# chiclet.net
KiCad netlist of a schematic drawn in EAGLE
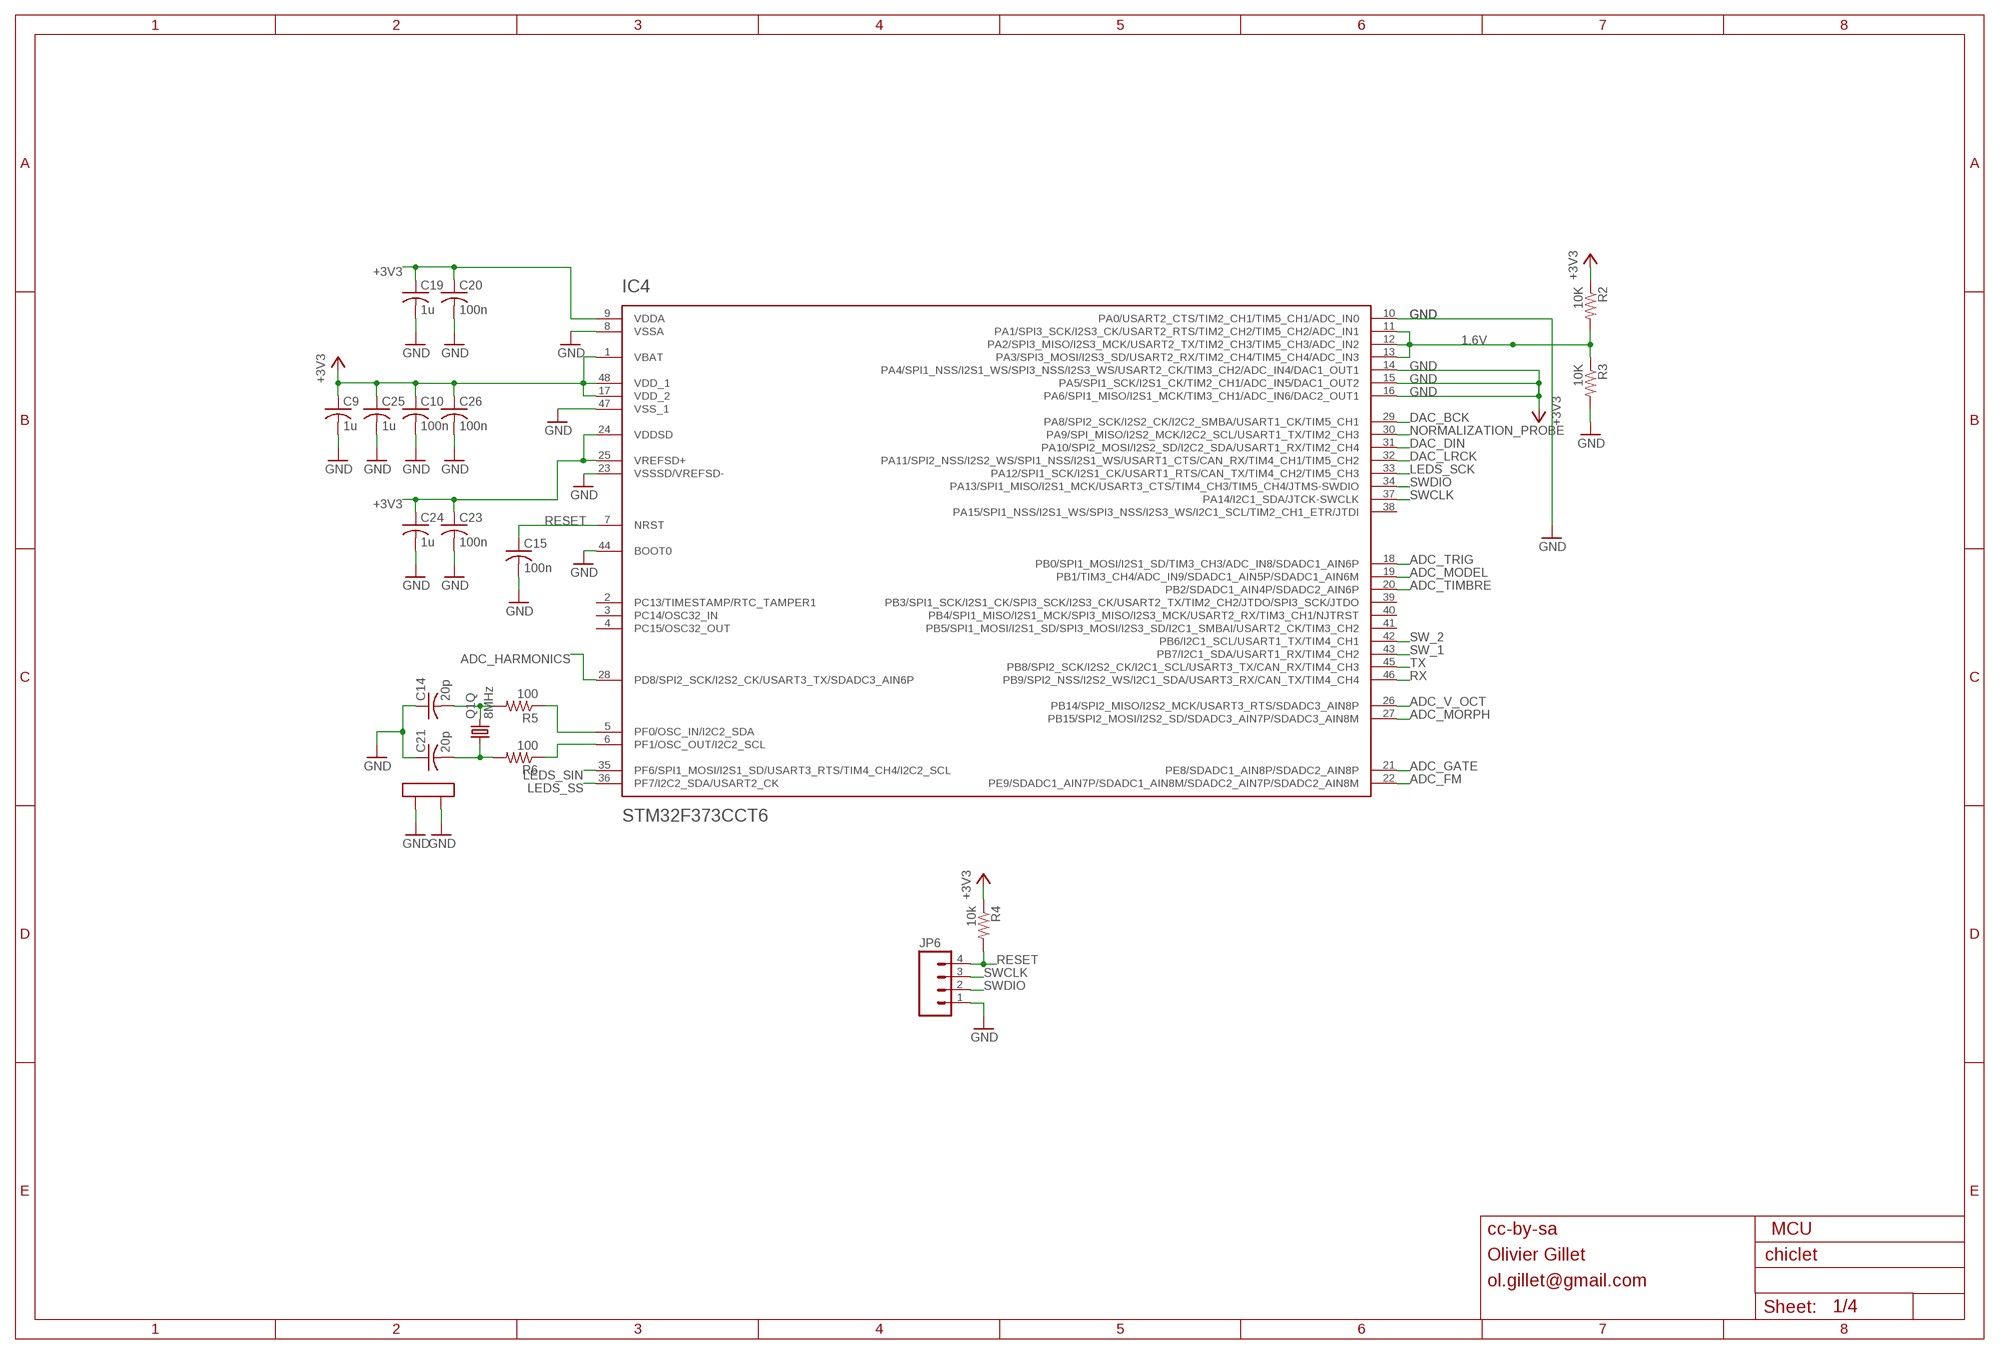
[diagram p0: schematic, sheet 1]
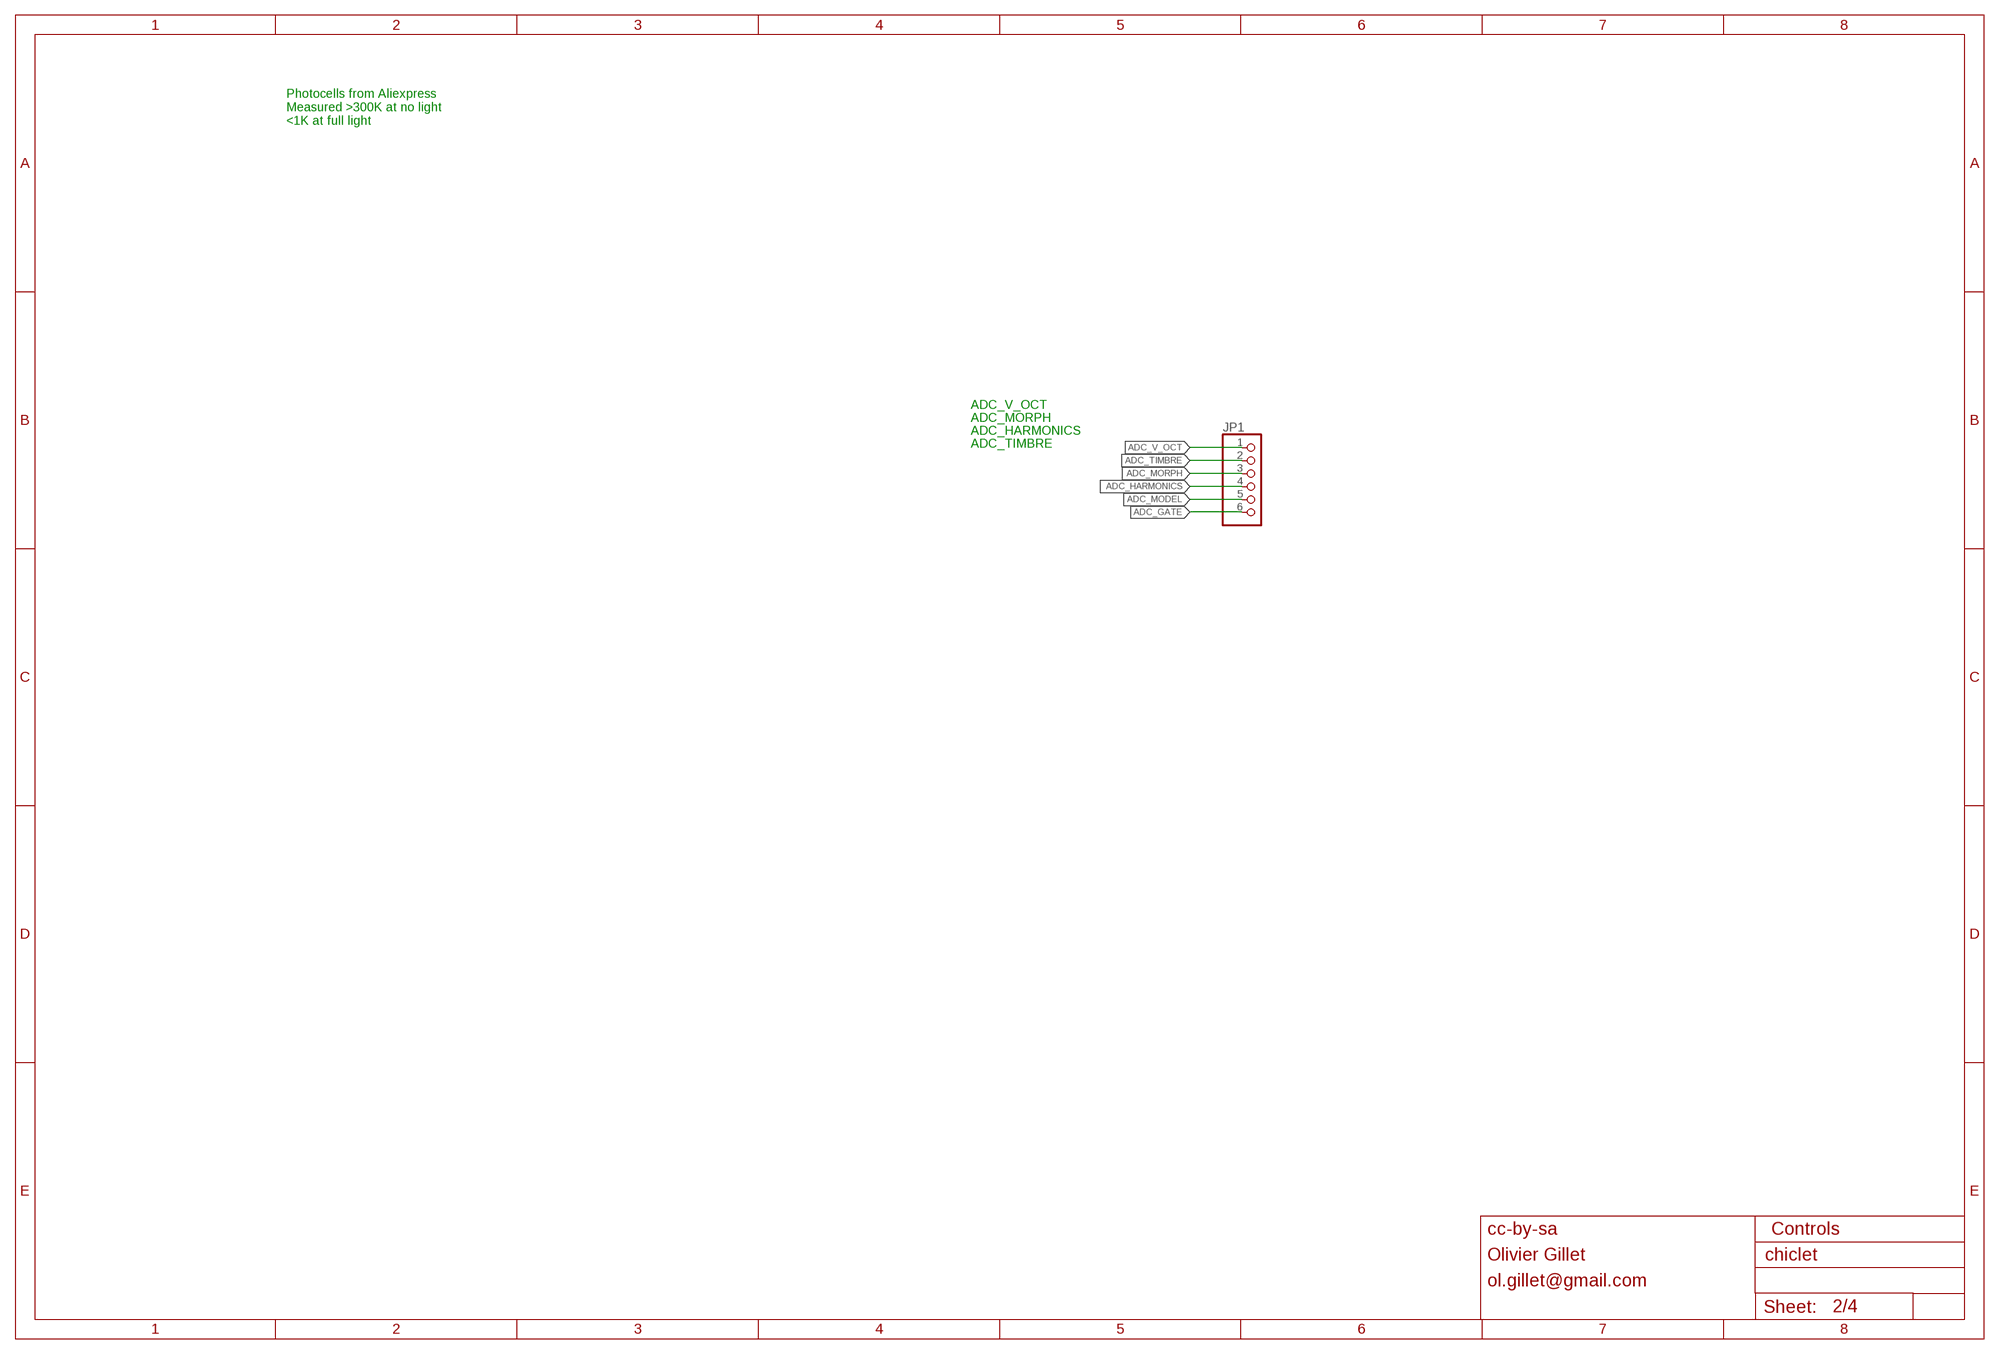
[diagram p1: schematic, sheet 2]
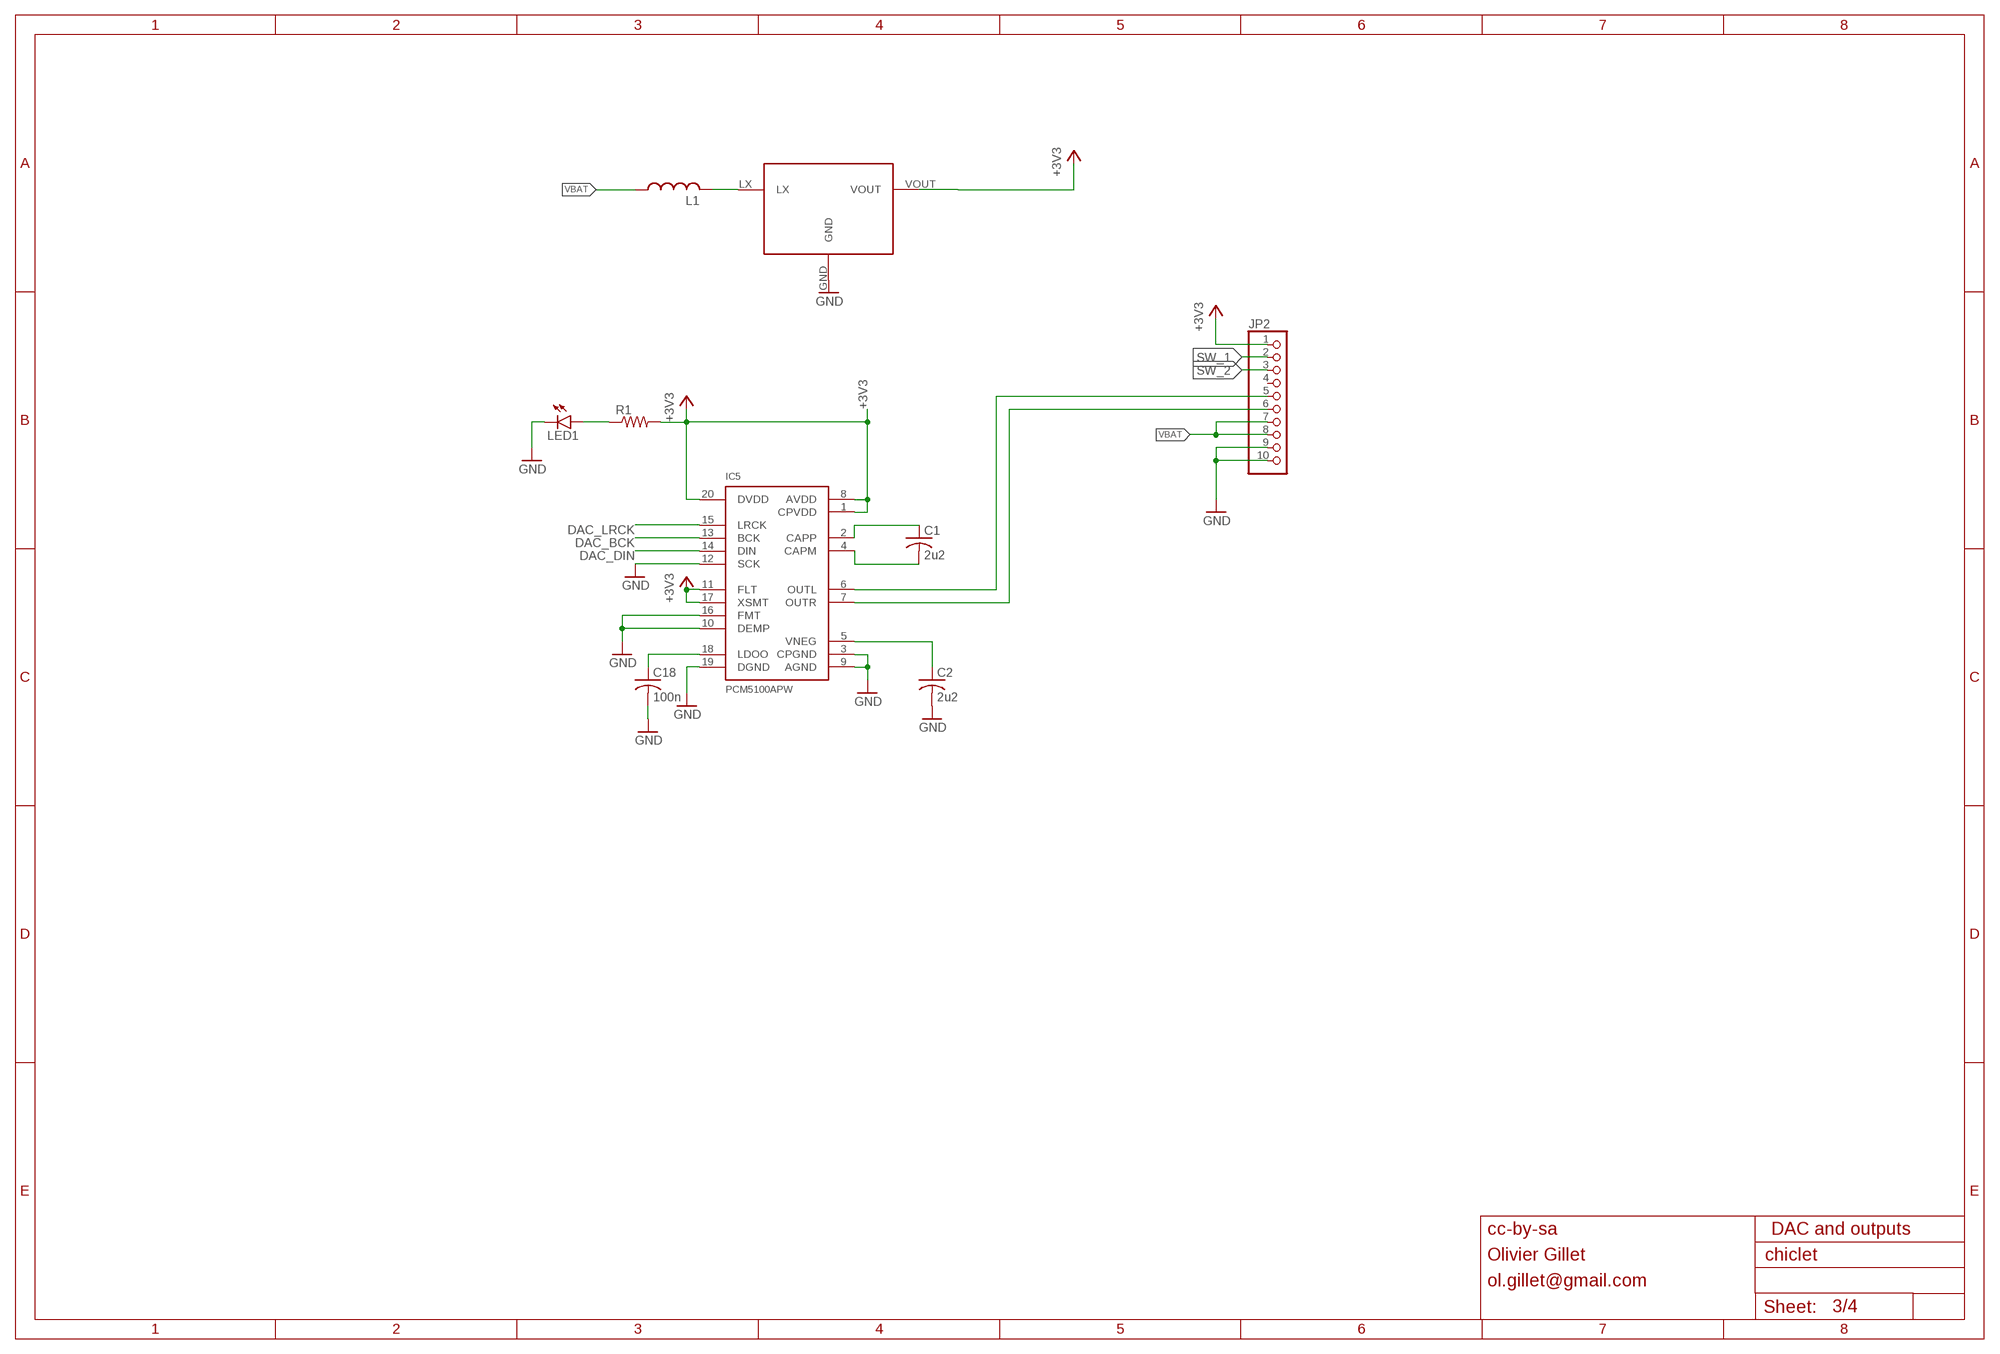
[diagram p2: schematic, sheet 3]
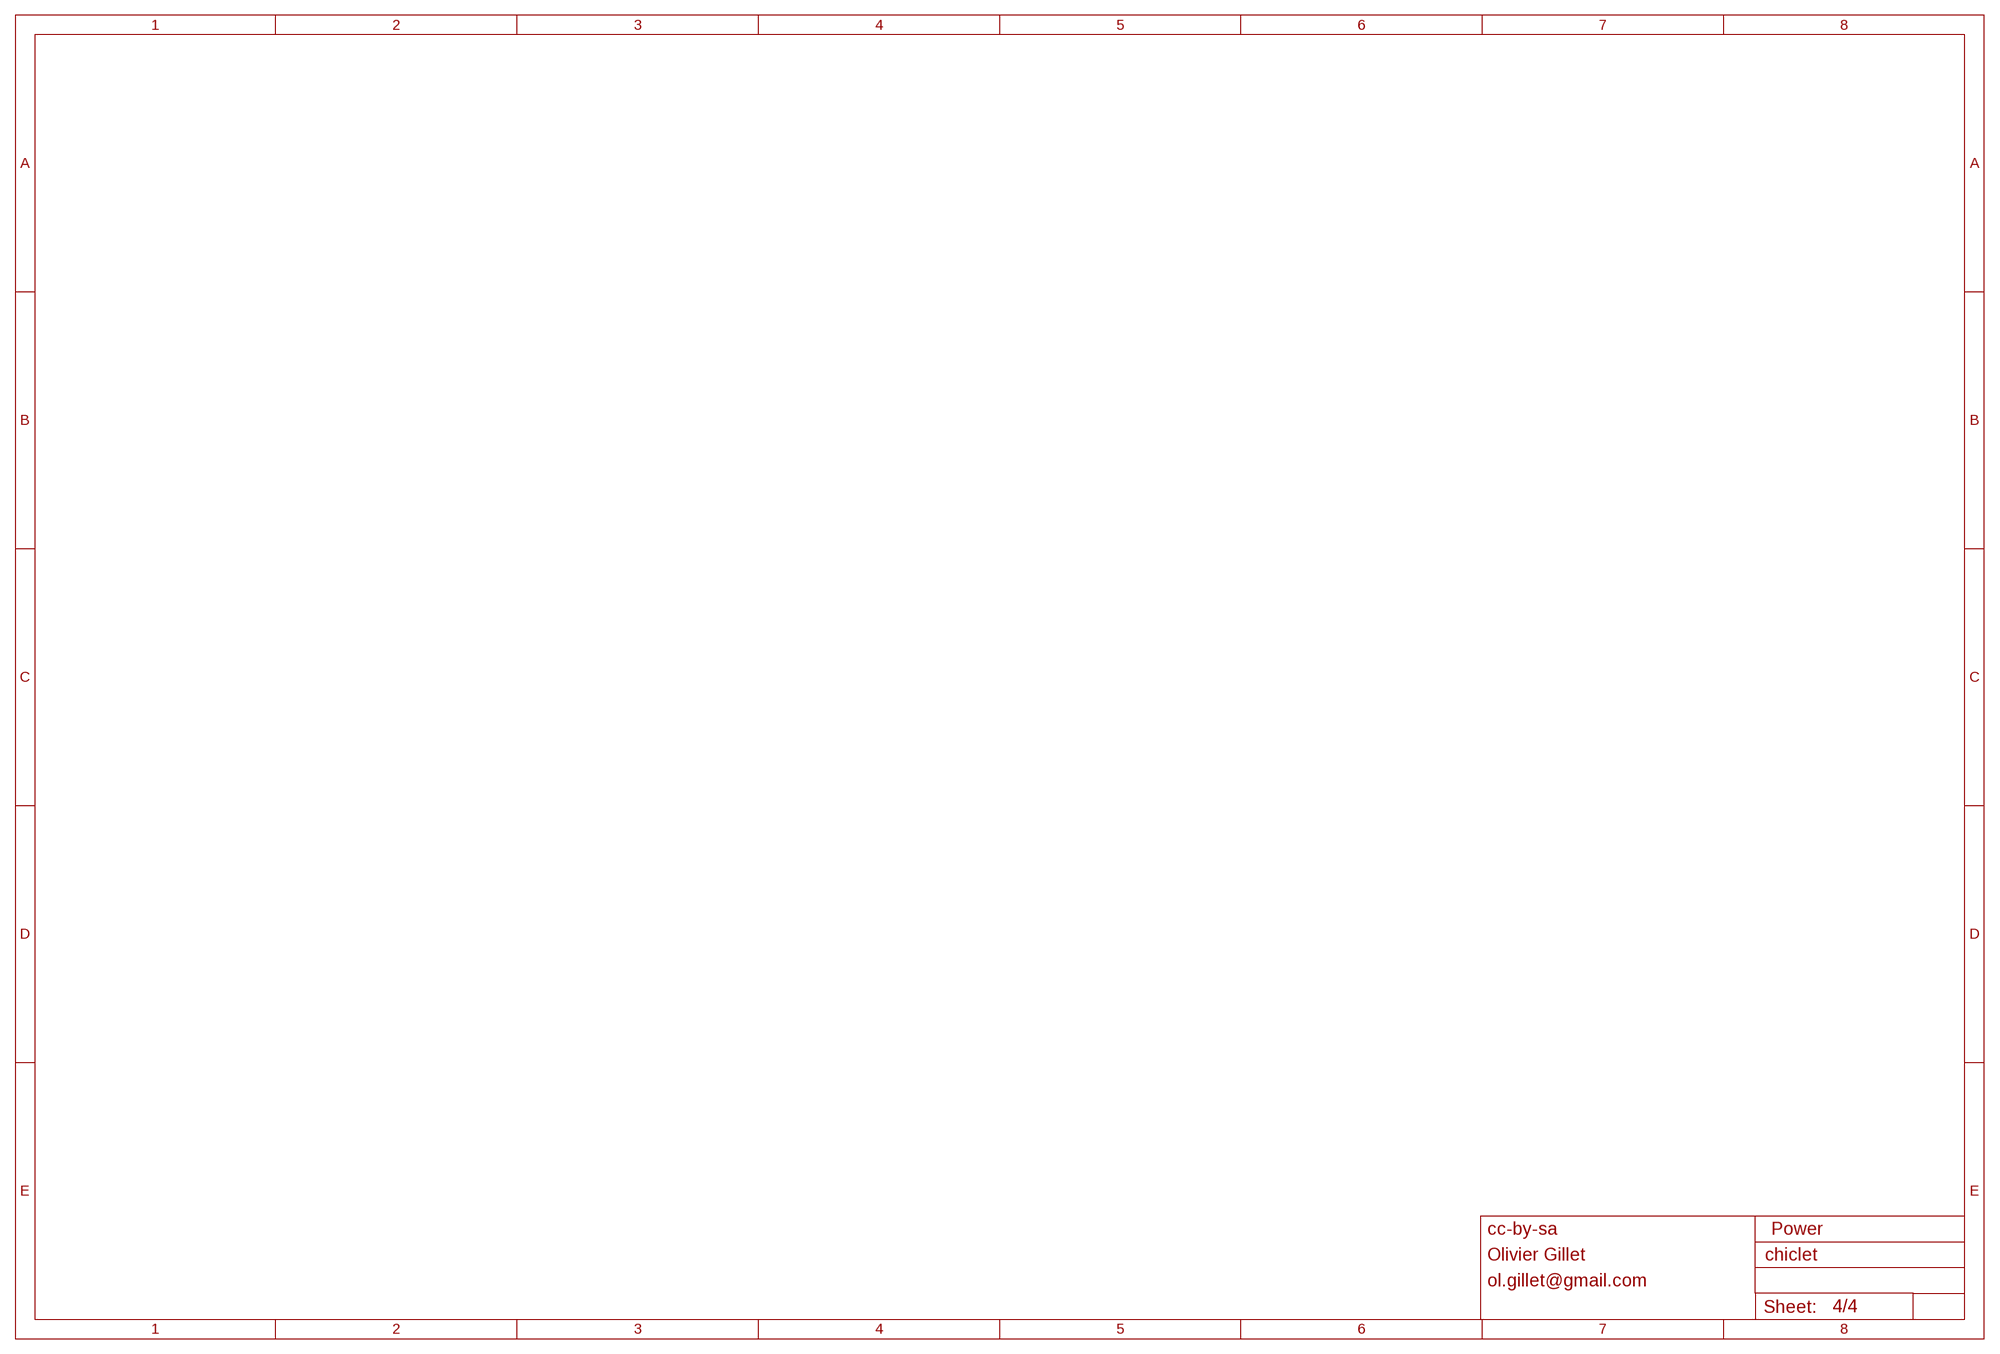
[diagram p3: schematic, sheet 4]

(export (version "E")
  (design (tool "Eeschema 10.0.6"))
  (components
    (comp (ref "C1")
      (value "2u2")
      (footprint "eagle-import:C0805K")
      (libsource (lib "eagle-import") (part "C-USC0805K"))
    )
    (comp (ref "C2")
      (value "2u2")
      (footprint "eagle-import:C0805K")
      (libsource (lib "eagle-import") (part "C-USC0805K"))
    )
    (comp (ref "C18")
      (value "100n")
      (footprint "eagle-import:C0805K")
      (libsource (lib "eagle-import") (part "C-USC0805K"))
    )
    (comp (ref "IC5")
      (value "PCM5100APW")
      (footprint "eagle-import:SSOP20")
      (libsource (lib "eagle-import") (part "PCM5100PW"))
    )
    (comp (ref "JP2")
      (value "PINHD-1X10")
      (footprint "eagle-import:1X10")
      (libsource (lib "eagle-import") (part "PINHD-1X10"))
    )
    (comp (ref "L1")
      (value "L-USL2825P")
      (footprint "eagle-import:L2825P")
      (libsource (lib "eagle-import") (part "L-USL2825P"))
    )
    (comp (ref "LED1")
      (value "LEDSML0805")
      (footprint "eagle-import:SML0805")
      (libsource (lib "eagle-import") (part "LEDSML0805"))
    )
    (comp (ref "R1")
      (value "R-US_R0805")
      (footprint "eagle-import:R0805")
      (libsource (lib "eagle-import") (part "R-US_R0805"))
    )
    (comp (ref "U$1")
      (value "QX2304L33E")
      (footprint "eagle-import:SOT89-R")
      (libsource (lib "eagle-import") (part "QX2304L33E"))
    )
    (comp (ref "JP1")
      (value "PINHD-1X6")
      (footprint "eagle-import:1X06")
      (libsource (lib "eagle-import") (part "PINHD-1X6"))
    )
    (comp (ref "C9")
      (value "1u")
      (footprint "eagle-import:C0805")
      (libsource (lib "eagle-import") (part "C-USC0805"))
    )
    (comp (ref "C10")
      (value "100n")
      (footprint "eagle-import:C0805")
      (libsource (lib "eagle-import") (part "C-USC0805"))
    )
    (comp (ref "C14")
      (value "20p")
      (footprint "eagle-import:C0805")
      (libsource (lib "eagle-import") (part "C-USC0805"))
    )
    (comp (ref "C15")
      (value "100n")
      (footprint "eagle-import:C0805")
      (libsource (lib "eagle-import") (part "C-USC0805"))
    )
    (comp (ref "C19")
      (value "1u")
      (footprint "eagle-import:C0805")
      (libsource (lib "eagle-import") (part "C-USC0805"))
    )
    (comp (ref "C20")
      (value "100n")
      (footprint "eagle-import:C0805")
      (libsource (lib "eagle-import") (part "C-USC0805"))
    )
    (comp (ref "C21")
      (value "20p")
      (footprint "eagle-import:C0805")
      (libsource (lib "eagle-import") (part "C-USC0805"))
    )
    (comp (ref "C23")
      (value "100n")
      (footprint "eagle-import:C0805")
      (libsource (lib "eagle-import") (part "C-USC0805"))
    )
    (comp (ref "C24")
      (value "1u")
      (footprint "eagle-import:C0805")
      (libsource (lib "eagle-import") (part "C-USC0805"))
    )
    (comp (ref "C25")
      (value "1u")
      (footprint "eagle-import:C0805")
      (libsource (lib "eagle-import") (part "C-USC0805"))
    )
    (comp (ref "C26")
      (value "100n")
      (footprint "eagle-import:C0805")
      (libsource (lib "eagle-import") (part "C-USC0805"))
    )
    (comp (ref "IC4")
      (value "STM32F373CCT6")
      (footprint "eagle-import:LQFP48")
      (libsource (lib "eagle-import") (part "STM32F373C"))
    )
    (comp (ref "JP6")
      (value "M04PTH")
      (footprint "eagle-import:1X04")
      (libsource (lib "eagle-import") (part "M04PTH"))
    )
    (comp (ref "Q1")
      (value "8MHz")
      (footprint "eagle-import:CTS406")
      (libsource (lib "eagle-import") (part "CRYSTAL"))
    )
    (comp (ref "R2")
      (value "10K")
      (footprint "eagle-import:M0805")
      (libsource (lib "eagle-import") (part "R-US_M0805"))
    )
    (comp (ref "R3")
      (value "10K")
      (footprint "eagle-import:M0805")
      (libsource (lib "eagle-import") (part "R-US_M0805"))
    )
    (comp (ref "R4")
      (value "10k")
      (footprint "eagle-import:M0805")
      (libsource (lib "eagle-import") (part "R-US_M0805"))
    )
    (comp (ref "R5")
      (value "100")
      (footprint "eagle-import:M0805")
      (libsource (lib "eagle-import") (part "R-US_M0805"))
    )
    (comp (ref "R6")
      (value "100")
      (footprint "eagle-import:M0805")
      (libsource (lib "eagle-import") (part "R-US_M0805"))
    )
  )
  (nets
    (net (code "1") (name "+3V3") (class "Default")
      (node (ref "C10") (pin "1") (pinfunction "1_1") (pintype "passive"))
      (node (ref "C19") (pin "1") (pinfunction "1_1") (pintype "passive"))
      (node (ref "C20") (pin "1") (pinfunction "1_1") (pintype "passive"))
      (node (ref "C23") (pin "1") (pinfunction "1_1") (pintype "passive"))
      (node (ref "C24") (pin "1") (pinfunction "1_1") (pintype "passive"))
      (node (ref "C25") (pin "1") (pinfunction "1_1") (pintype "passive"))
      (node (ref "C26") (pin "1") (pinfunction "1_1") (pintype "passive"))
      (node (ref "C9") (pin "1") (pinfunction "1_1") (pintype "passive"))
      (node (ref "IC4") (pin "1") (pinfunction "VBAT_1") (pintype "power_in"))
      (node (ref "IC4") (pin "14") (pinfunction "PA4/SPI1_NSS/I2S1_WS/SPI3_NSS/I2S3_WS/USART2_CK/TIM3_CH2/ADC_IN4/DAC1_OUT1_14") (pintype "bidirectional"))
      (node (ref "IC4") (pin "15") (pinfunction "PA5/SPI1_SCK/I2S1_CK/TIM2_CH1/ADC_IN5/DAC1_OUT2_15") (pintype "bidirectional"))
      (node (ref "IC4") (pin "16") (pinfunction "PA6/SPI1_MISO/I2S1_MCK/TIM3_CH1/ADC_IN6/DAC2_OUT1_16") (pintype "bidirectional"))
      (node (ref "IC4") (pin "17") (pinfunction "VDD_2_17") (pintype "power_in"))
      (node (ref "IC4") (pin "24") (pinfunction "VDDSD_24") (pintype "power_in"))
      (node (ref "IC4") (pin "25") (pinfunction "VREFSD+_25") (pintype "power_in"))
      (node (ref "IC4") (pin "48") (pinfunction "VDD_1_48") (pintype "power_in"))
      (node (ref "IC4") (pin "9") (pinfunction "VDDA_9") (pintype "power_in"))
      (node (ref "IC5") (pin "1") (pinfunction "CPVDD_1") (pintype "bidirectional"))
      (node (ref "IC5") (pin "11") (pinfunction "FLT_11") (pintype "input"))
      (node (ref "IC5") (pin "17") (pinfunction "XSMT_17") (pintype "input"))
      (node (ref "IC5") (pin "20") (pinfunction "DVDD_20") (pintype "power_in"))
      (node (ref "IC5") (pin "8") (pinfunction "AVDD_8") (pintype "power_in"))
      (node (ref "JP2") (pin "1") (pinfunction "1_1") (pintype "passive"))
      (node (ref "R1") (pin "2") (pinfunction "2_2") (pintype "passive"))
      (node (ref "R2") (pin "1") (pinfunction "1_1") (pintype "passive"))
      (node (ref "R4") (pin "1") (pinfunction "1_1") (pintype "passive"))
      (node (ref "U$1") (pin "VOUT") (pinfunction "VOUT_VOUT") (pintype "bidirectional"))
    )
    (net (code "2") (name "1.6V") (class "Default")
      (node (ref "IC4") (pin "11") (pinfunction "PA1/SPI3_SCK/I2S3_CK/USART2_RTS/TIM2_CH2/TIM5_CH2/ADC_IN1_11") (pintype "bidirectional"))
      (node (ref "IC4") (pin "12") (pinfunction "PA2/SPI3_MISO/I2S3_MCK/USART2_TX/TIM2_CH3/TIM5_CH3/ADC_IN2_12") (pintype "bidirectional"))
      (node (ref "IC4") (pin "13") (pinfunction "PA3/SPI3_MOSI/I2S3_SD/USART2_RX/TIM2_CH4/TIM5_CH4/ADC_IN3_13") (pintype "bidirectional"))
      (node (ref "R2") (pin "2") (pinfunction "2_2") (pintype "passive"))
      (node (ref "R3") (pin "1") (pinfunction "1_1") (pintype "passive"))
    )
    (net (code "3") (name "ADC_FM") (class "Default")
      (node (ref "IC4") (pin "22") (pinfunction "PE9/SDADC1_AIN7P/SDADC1_AIN8M/SDADC2_AIN7P/SDADC2_AIN8M_22") (pintype "bidirectional"))
    )
    (net (code "4") (name "ADC_GATE") (class "Default")
      (node (ref "IC4") (pin "21") (pinfunction "PE8/SDADC1_AIN8P/SDADC2_AIN8P_21") (pintype "bidirectional"))
      (node (ref "JP1") (pin "6") (pinfunction "6_6") (pintype "passive"))
    )
    (net (code "5") (name "ADC_HARMONICS") (class "Default")
      (node (ref "IC4") (pin "28") (pinfunction "PD8/SPI2_SCK/I2S2_CK/USART3_TX/SDADC3_AIN6P_28") (pintype "bidirectional"))
      (node (ref "JP1") (pin "4") (pinfunction "4_4") (pintype "passive"))
    )
    (net (code "6") (name "ADC_MODEL") (class "Default")
      (node (ref "IC4") (pin "19") (pinfunction "PB1/TIM3_CH4/ADC_IN9/SDADC1_AIN5P/SDADC1_AIN6M_19") (pintype "bidirectional"))
      (node (ref "JP1") (pin "5") (pinfunction "5_5") (pintype "passive"))
    )
    (net (code "7") (name "ADC_MORPH") (class "Default")
      (node (ref "IC4") (pin "27") (pinfunction "PB15/SPI2_MOSI/I2S2_SD/SDADC3_AIN7P/SDADC3_AIN8M_27") (pintype "bidirectional"))
      (node (ref "JP1") (pin "3") (pinfunction "3_3") (pintype "passive"))
    )
    (net (code "8") (name "ADC_TIMBRE") (class "Default")
      (node (ref "IC4") (pin "20") (pinfunction "PB2/SDADC1_AIN4P/SDADC2_AIN6P_20") (pintype "bidirectional"))
      (node (ref "JP1") (pin "2") (pinfunction "2_2") (pintype "passive"))
    )
    (net (code "9") (name "ADC_TRIG") (class "Default")
      (node (ref "IC4") (pin "18") (pinfunction "PB0/SPI1_MOSI/I2S1_SD/TIM3_CH3/ADC_IN8/SDADC1_AIN6P_18") (pintype "bidirectional"))
    )
    (net (code "10") (name "ADC_V_OCT") (class "Default")
      (node (ref "IC4") (pin "26") (pinfunction "PB14/SPI2_MISO/I2S2_MCK/USART3_RTS/SDADC3_AIN8P_26") (pintype "bidirectional"))
      (node (ref "JP1") (pin "1") (pinfunction "1_1") (pintype "passive"))
    )
    (net (code "11") (name "DAC_BCK") (class "Default")
      (node (ref "IC4") (pin "29") (pinfunction "PA8/SPI2_SCK/I2S2_CK/I2C2_SMBA/USART1_CK/TIM5_CH1_29") (pintype "bidirectional"))
      (node (ref "IC5") (pin "13") (pinfunction "BCK_13") (pintype "input"))
    )
    (net (code "12") (name "DAC_DIN") (class "Default")
      (node (ref "IC4") (pin "31") (pinfunction "PA10/SPI2_MOSI/I2S2_SD/I2C2_SDA/USART1_RX/TIM2_CH4_31") (pintype "bidirectional"))
      (node (ref "IC5") (pin "14") (pinfunction "DIN_14") (pintype "input"))
    )
    (net (code "13") (name "DAC_LRCK") (class "Default")
      (node (ref "IC4") (pin "32") (pinfunction "PA11/SPI2_NSS/I2S2_WS/SPI1_NSS/I2S1_WS/USART1_CTS/CAN_RX/TIM4_CH1/TIM5_CH2_32") (pintype "bidirectional"))
      (node (ref "IC5") (pin "15") (pinfunction "LRCK_15") (pintype "input"))
    )
    (net (code "14") (name "GND") (class "Default")
      (node (ref "C10") (pin "2") (pinfunction "2_2") (pintype "passive"))
      (node (ref "C14") (pin "1") (pinfunction "1_1") (pintype "passive"))
      (node (ref "C15") (pin "2") (pinfunction "2_2") (pintype "passive"))
      (node (ref "C18") (pin "2") (pinfunction "2_2") (pintype "passive"))
      (node (ref "C19") (pin "2") (pinfunction "2_2") (pintype "passive"))
      (node (ref "C2") (pin "2") (pinfunction "2_2") (pintype "passive"))
      (node (ref "C20") (pin "2") (pinfunction "2_2") (pintype "passive"))
      (node (ref "C21") (pin "1") (pinfunction "1_1") (pintype "passive"))
      (node (ref "C23") (pin "2") (pinfunction "2_2") (pintype "passive"))
      (node (ref "C24") (pin "2") (pinfunction "2_2") (pintype "passive"))
      (node (ref "C25") (pin "2") (pinfunction "2_2") (pintype "passive"))
      (node (ref "C26") (pin "2") (pinfunction "2_2") (pintype "passive"))
      (node (ref "C9") (pin "2") (pinfunction "2_2") (pintype "passive"))
      (node (ref "IC4") (pin "10") (pinfunction "PA0/USART2_CTS/TIM2_CH1/TIM5_CH1/ADC_IN0_10") (pintype "bidirectional"))
      (node (ref "IC4") (pin "23") (pinfunction "VSSSD/VREFSD-_23") (pintype "power_in"))
      (node (ref "IC4") (pin "44") (pinfunction "BOOT0_44") (pintype "bidirectional"))
      (node (ref "IC4") (pin "47") (pinfunction "VSS_1_47") (pintype "power_in"))
      (node (ref "IC4") (pin "8") (pinfunction "VSSA_8") (pintype "power_in"))
      (node (ref "IC5") (pin "10") (pinfunction "DEMP_10") (pintype "input"))
      (node (ref "IC5") (pin "12") (pinfunction "SCK_12") (pintype "input"))
      (node (ref "IC5") (pin "16") (pinfunction "FMT_16") (pintype "input"))
      (node (ref "IC5") (pin "19") (pinfunction "DGND_19") (pintype "power_in"))
      (node (ref "IC5") (pin "3") (pinfunction "CPGND_3") (pintype "bidirectional"))
      (node (ref "IC5") (pin "9") (pinfunction "AGND_9") (pintype "power_in"))
      (node (ref "JP2") (pin "10") (pinfunction "10_10") (pintype "passive"))
      (node (ref "JP2") (pin "9") (pinfunction "9_9") (pintype "passive"))
      (node (ref "JP6") (pin "1") (pinfunction "1_1") (pintype "passive"))
      (node (ref "LED1") (pin "C") (pinfunction "C_C") (pintype "passive"))
      (node (ref "Q1") (pin "2") (pinfunction "LID1_2") (pintype "power_in"))
      (node (ref "Q1") (pin "4") (pinfunction "LID2_4") (pintype "power_in"))
      (node (ref "R3") (pin "2") (pinfunction "2_2") (pintype "passive"))
      (node (ref "U$1") (pin "GND") (pinfunction "GND_GND") (pintype "bidirectional"))
    )
    (net (code "15") (name "LEDS_SCK") (class "Default")
      (node (ref "IC4") (pin "33") (pinfunction "PA12/SPI1_SCK/I2S1_CK/USART1_RTS/CAN_TX/TIM4_CH2/TIM5_CH3_33") (pintype "bidirectional"))
    )
    (net (code "16") (name "LEDS_SIN") (class "Default")
      (node (ref "IC4") (pin "35") (pinfunction "PF6/SPI1_MOSI/I2S1_SD/USART3_RTS/TIM4_CH4/I2C2_SCL_35") (pintype "bidirectional"))
    )
    (net (code "17") (name "LEDS_SS") (class "Default")
      (node (ref "IC4") (pin "36") (pinfunction "PF7/I2C2_SDA/USART2_CK_36") (pintype "bidirectional"))
    )
    (net (code "18") (name "NORMALIZATION_PROBE") (class "Default")
      (node (ref "IC4") (pin "30") (pinfunction "PA9/SPI_MISO/I2S2_MCK/I2C2_SCL/USART1_TX/TIM2_CH3_30") (pintype "bidirectional"))
    )
    (net (code "19") (name "Net-(C21-Pad2)") (class "Default")
      (node (ref "C21") (pin "2") (pinfunction "2_2") (pintype "passive"))
      (node (ref "Q1") (pin "1") (pinfunction "1_1") (pintype "passive"))
      (node (ref "R6") (pin "2") (pinfunction "2_2") (pintype "passive"))
    )
    (net (code "20") (name "Net-(IC4-PF0{slash}OSC_IN{slash}I2C2_SDA)") (class "Default")
      (node (ref "IC4") (pin "5") (pinfunction "PF0/OSC_IN/I2C2_SDA_5") (pintype "bidirectional"))
      (node (ref "R5") (pin "1") (pinfunction "1_1") (pintype "passive"))
    )
    (net (code "21") (name "Net-(IC4-PF1{slash}OSC_OUT{slash}I2C2_SCL)") (class "Default")
      (node (ref "IC4") (pin "6") (pinfunction "PF1/OSC_OUT/I2C2_SCL_6") (pintype "bidirectional"))
      (node (ref "R6") (pin "1") (pinfunction "1_1") (pintype "passive"))
    )
    (net (code "22") (name "Net-(IC5-CAPM)") (class "Default")
      (node (ref "C1") (pin "2") (pinfunction "2_2") (pintype "passive"))
      (node (ref "IC5") (pin "4") (pinfunction "CAPM_4") (pintype "bidirectional"))
    )
    (net (code "23") (name "Net-(IC5-CAPP)") (class "Default")
      (node (ref "C1") (pin "1") (pinfunction "1_1") (pintype "passive"))
      (node (ref "IC5") (pin "2") (pinfunction "CAPP_2") (pintype "bidirectional"))
    )
    (net (code "24") (name "Net-(IC5-LDOO)") (class "Default")
      (node (ref "C18") (pin "1") (pinfunction "1_1") (pintype "passive"))
      (node (ref "IC5") (pin "18") (pinfunction "LDOO_18") (pintype "bidirectional"))
    )
    (net (code "25") (name "Net-(IC5-OUTL)") (class "Default")
      (node (ref "IC5") (pin "6") (pinfunction "OUTL_6") (pintype "output"))
      (node (ref "JP2") (pin "5") (pinfunction "5_5") (pintype "passive"))
    )
    (net (code "26") (name "Net-(IC5-OUTR)") (class "Default")
      (node (ref "IC5") (pin "7") (pinfunction "OUTR_7") (pintype "output"))
      (node (ref "JP2") (pin "6") (pinfunction "6_6") (pintype "passive"))
    )
    (net (code "27") (name "Net-(IC5-VNEG)") (class "Default")
      (node (ref "C2") (pin "1") (pinfunction "1_1") (pintype "passive"))
      (node (ref "IC5") (pin "5") (pinfunction "VNEG_5") (pintype "input"))
    )
    (net (code "28") (name "Net-(L1-Pad2)") (class "Default")
      (node (ref "L1") (pin "2") (pinfunction "2_2") (pintype "passive"))
      (node (ref "U$1") (pin "LX") (pinfunction "LX_LX") (pintype "bidirectional"))
    )
    (net (code "29") (name "Net-(LED1-PadA)") (class "Default")
      (node (ref "LED1") (pin "A") (pinfunction "A_A") (pintype "passive"))
      (node (ref "R1") (pin "1") (pinfunction "1_1") (pintype "passive"))
    )
    (net (code "30") (name "Net-(Q1B-2)") (class "Default")
      (node (ref "C14") (pin "2") (pinfunction "2_2") (pintype "passive"))
      (node (ref "Q1") (pin "3") (pinfunction "2_3") (pintype "passive"))
      (node (ref "R5") (pin "2") (pinfunction "2_2") (pintype "passive"))
    )
    (net (code "31") (name "RESET") (class "Default")
      (node (ref "C15") (pin "1") (pinfunction "1_1") (pintype "passive"))
      (node (ref "IC4") (pin "7") (pinfunction "NRST_7") (pintype "bidirectional"))
      (node (ref "JP6") (pin "4") (pinfunction "4_4") (pintype "passive"))
      (node (ref "R4") (pin "2") (pinfunction "2_2") (pintype "passive"))
    )
    (net (code "32") (name "RX") (class "Default")
      (node (ref "IC4") (pin "46") (pinfunction "PB9/SPI2_NSS/I2S2_WS/I2C1_SDA/USART3_RX/CAN_TX/TIM4_CH4_46") (pintype "bidirectional"))
    )
    (net (code "33") (name "SWCLK") (class "Default")
      (node (ref "IC4") (pin "37") (pinfunction "PA14/I2C1_SDA/JTCK-SWCLK_37") (pintype "bidirectional"))
      (node (ref "JP6") (pin "3") (pinfunction "3_3") (pintype "passive"))
    )
    (net (code "34") (name "SWDIO") (class "Default")
      (node (ref "IC4") (pin "34") (pinfunction "PA13/SPI1_MISO/I2S1_MCK/USART3_CTS/TIM4_CH3/TIM5_CH4/JTMS-SWDIO_34") (pintype "bidirectional"))
      (node (ref "JP6") (pin "2") (pinfunction "2_2") (pintype "passive"))
    )
    (net (code "35") (name "SW_1") (class "Default")
      (node (ref "IC4") (pin "43") (pinfunction "PB7/I2C1_SDA/USART1_RX/TIM4_CH2_43") (pintype "bidirectional"))
      (node (ref "JP2") (pin "2") (pinfunction "2_2") (pintype "passive"))
    )
    (net (code "36") (name "SW_2") (class "Default")
      (node (ref "IC4") (pin "42") (pinfunction "PB6/I2C1_SCL/USART1_TX/TIM4_CH1_42") (pintype "bidirectional"))
      (node (ref "JP2") (pin "3") (pinfunction "3_3") (pintype "passive"))
    )
    (net (code "37") (name "TX") (class "Default")
      (node (ref "IC4") (pin "45") (pinfunction "PB8/SPI2_SCK/I2S2_CK/I2C1_SCL/USART3_TX/CAN_RX/TIM4_CH3_45") (pintype "bidirectional"))
    )
    (net (code "38") (name "VBAT") (class "Default")
      (node (ref "JP2") (pin "7") (pinfunction "7_7") (pintype "passive"))
      (node (ref "JP2") (pin "8") (pinfunction "8_8") (pintype "passive"))
      (node (ref "L1") (pin "1") (pinfunction "1_1") (pintype "passive"))
    )
    (net (code "39") (name "unconnected-(IC4-PA15{slash}SPI1_NSS{slash}I2S1_WS{slash}SPI3_NSS{slash}I2S3_WS{slash}I2C1_SCL{slash}TIM2_CH1_ETR{slash}JTDI-Pad38)") (class "Default")
      (node (ref "IC4") (pin "38") (pinfunction "PA15/SPI1_NSS/I2S1_WS/SPI3_NSS/I2S3_WS/I2C1_SCL/TIM2_CH1_ETR/JTDI_38") (pintype "bidirectional"))
    )
    (net (code "40") (name "unconnected-(IC4-PB3{slash}SPI1_SCK{slash}I2S1_CK{slash}SPI3_SCK{slash}I2S3_CK{slash}USART2_TX{slash}TIM2_CH2{slash}JTDO{slash}SPI3_SCK{slash}JTDO-Pad39)") (class "Default")
      (node (ref "IC4") (pin "39") (pinfunction "PB3/SPI1_SCK/I2S1_CK/SPI3_SCK/I2S3_CK/USART2_TX/TIM2_CH2/JTDO/SPI3_SCK/JTDO_39") (pintype "bidirectional"))
    )
    (net (code "41") (name "unconnected-(IC4-PB4{slash}SPI1_MISO{slash}I2S1_MCK{slash}SPI3_MISO{slash}I2S3_MCK{slash}USART2_RX{slash}TIM3_CH1{slash}NJTRST-Pad40)") (class "Default")
      (node (ref "IC4") (pin "40") (pinfunction "PB4/SPI1_MISO/I2S1_MCK/SPI3_MISO/I2S3_MCK/USART2_RX/TIM3_CH1/NJTRST_40") (pintype "bidirectional"))
    )
    (net (code "42") (name "unconnected-(IC4-PB5{slash}SPI1_MOSI{slash}I2S1_SD{slash}SPI3_MOSI{slash}I2S3_SD{slash}I2C1_SMBAI{slash}USART2_CK{slash}TIM3_CH2-Pad41)") (class "Default")
      (node (ref "IC4") (pin "41") (pinfunction "PB5/SPI1_MOSI/I2S1_SD/SPI3_MOSI/I2S3_SD/I2C1_SMBAI/USART2_CK/TIM3_CH2_41") (pintype "bidirectional"))
    )
    (net (code "43") (name "unconnected-(IC4-PC13{slash}TIMESTAMP{slash}RTC_TAMPER1-Pad2)") (class "Default")
      (node (ref "IC4") (pin "2") (pinfunction "PC13/TIMESTAMP/RTC_TAMPER1_2") (pintype "bidirectional"))
    )
    (net (code "44") (name "unconnected-(IC4-PC14{slash}OSC32_IN-Pad3)") (class "Default")
      (node (ref "IC4") (pin "3") (pinfunction "PC14/OSC32_IN_3") (pintype "bidirectional"))
    )
    (net (code "45") (name "unconnected-(IC4-PC15{slash}OSC32_OUT-Pad4)") (class "Default")
      (node (ref "IC4") (pin "4") (pinfunction "PC15/OSC32_OUT_4") (pintype "bidirectional"))
    )
    (net (code "46") (name "unconnected-(JP2-Pad4)") (class "Default")
      (node (ref "JP2") (pin "4") (pinfunction "4_4") (pintype "passive"))
    )
  )
)
